# rev00.net
KiCad netlist of a schematic drawn in EAGLE
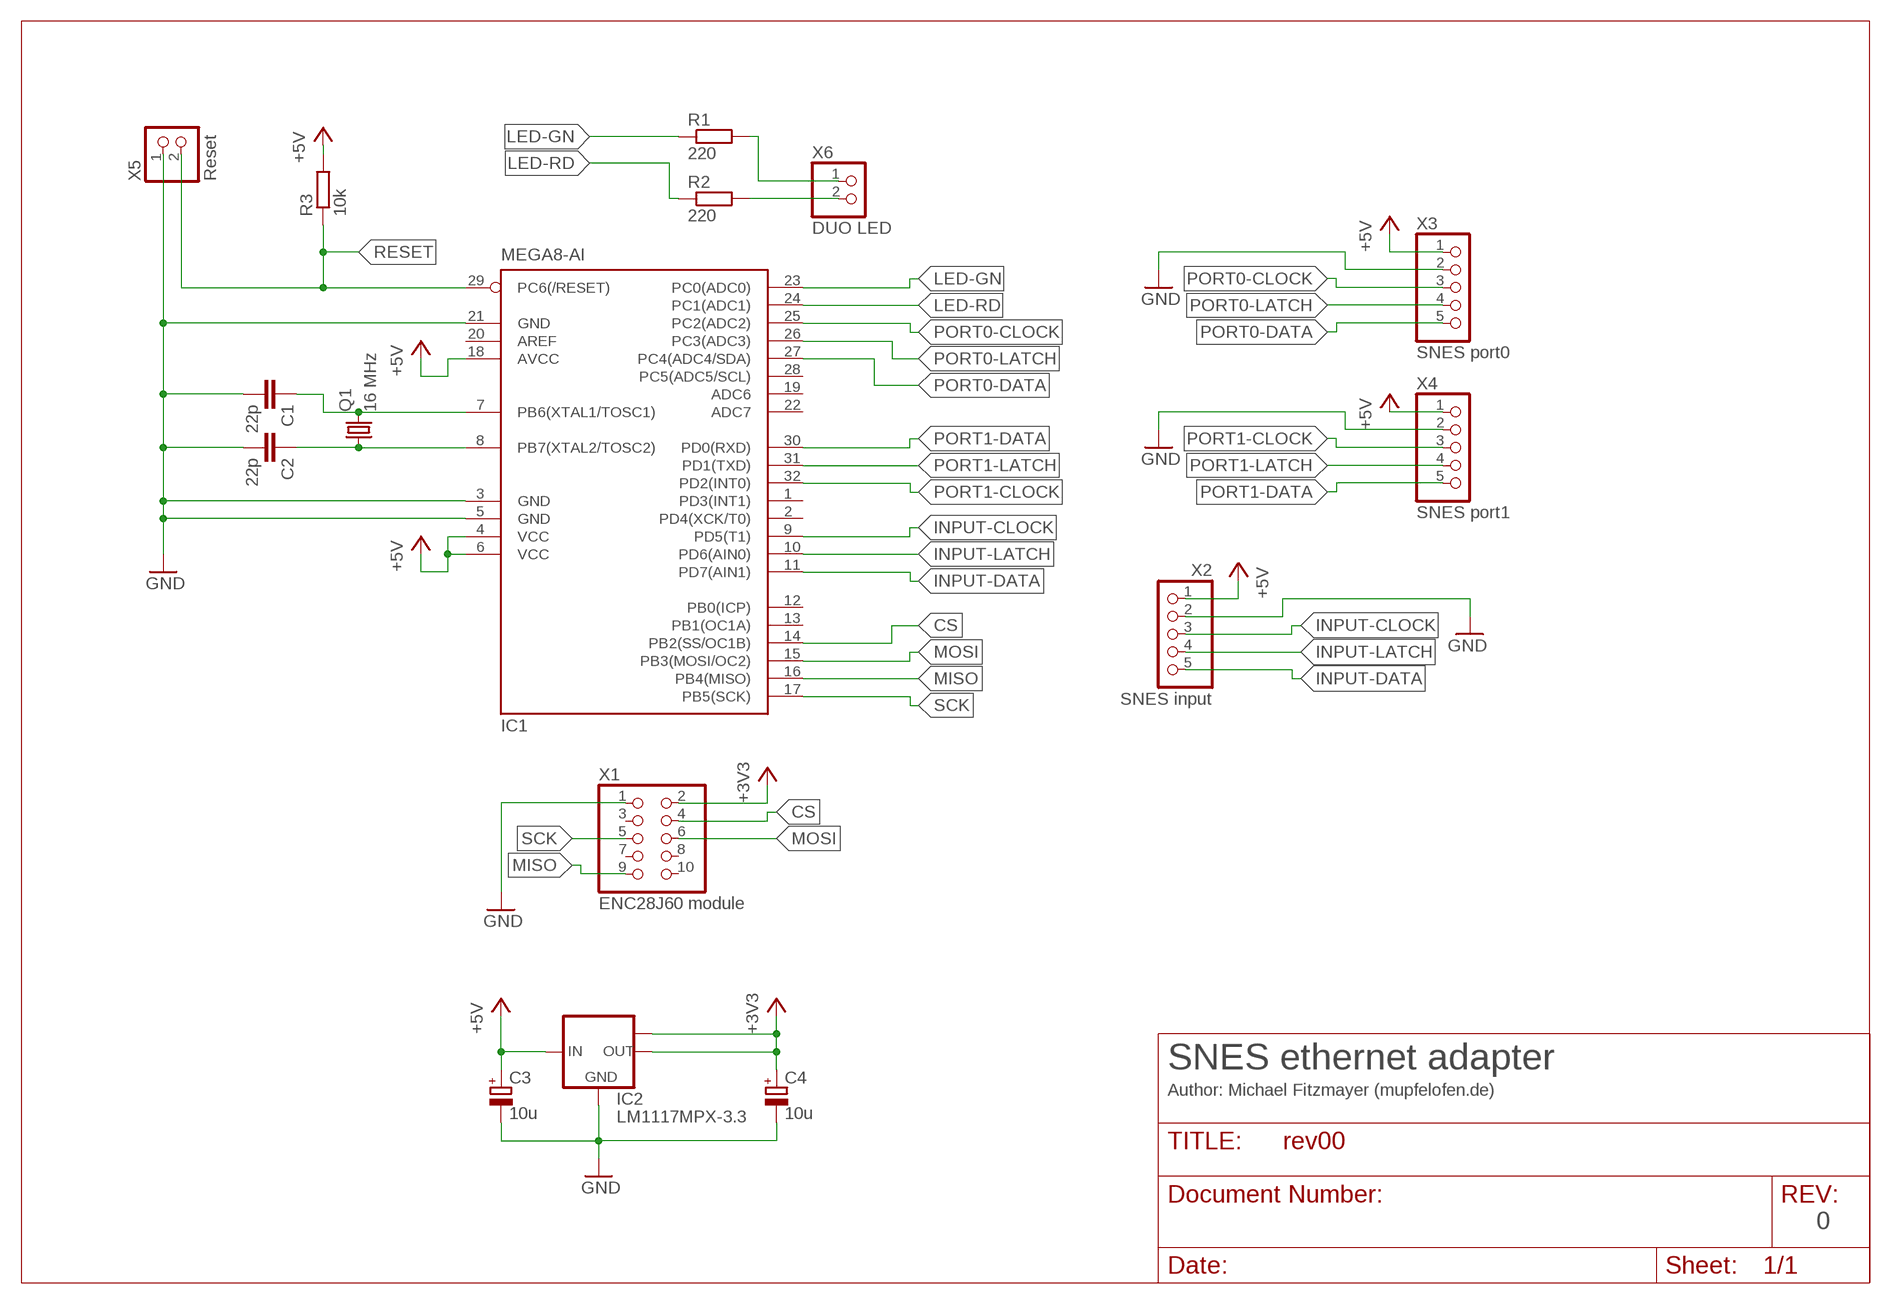
[diagram p0: schematic, sheet 1]

(export (version "E")
  (design (tool "Eeschema 10.0.6"))
  (components
    (comp (ref "C1")
      (value "22p")
      (footprint "eagle-import:C1206")
      (libsource (lib "eagle-import") (part "C-EUC1206"))
    )
    (comp (ref "C2")
      (value "22p")
      (footprint "eagle-import:C1206")
      (libsource (lib "eagle-import") (part "C-EUC1206"))
    )
    (comp (ref "C3")
      (value "10u")
      (footprint "eagle-import:C_6032-28R")
      (libsource (lib "eagle-import") (part "CPOL-EUC/6032-28R"))
    )
    (comp (ref "C4")
      (value "10u")
      (footprint "eagle-import:C_6032-28R")
      (libsource (lib "eagle-import") (part "CPOL-EUC/6032-28R"))
    )
    (comp (ref "IC1")
      (value "MEGA8-AI")
      (footprint "eagle-import:TQFP32-08")
      (fields (field (name "MPN") "ATMEGA8-16AU"))
      (libsource (lib "eagle-import") (part "MEGA8-AI"))
    )
    (comp (ref "IC2")
      (value "LM1117MPX-3.3")
      (footprint "eagle-import:SOT223")
      (libsource (lib "eagle-import") (part "LM1117MPX-3.3"))
    )
    (comp (ref "Q1")
      (value "16 MHz")
      (footprint "eagle-import:SM49")
      (libsource (lib "eagle-import") (part "CRYSTALSM49"))
    )
    (comp (ref "R1")
      (value "220")
      (footprint "eagle-import:R1206")
      (libsource (lib "eagle-import") (part "R-EU_R1206"))
    )
    (comp (ref "R2")
      (value "220")
      (footprint "eagle-import:R1206")
      (libsource (lib "eagle-import") (part "R-EU_R1206"))
    )
    (comp (ref "R3")
      (value "10k")
      (footprint "eagle-import:R1206")
      (libsource (lib "eagle-import") (part "R-EU_R1206"))
    )
    (comp (ref "X1")
      (value "ENC28J60 module")
      (footprint "eagle-import:2X05SMD")
      (libsource (lib "eagle-import") (part "PINHD-2X5_2.54-SMD"))
    )
    (comp (ref "X2")
      (value "SNES input")
      (footprint "eagle-import:1X05SMD")
      (libsource (lib "eagle-import") (part "PINHD-1X5_2.54-SMD"))
    )
    (comp (ref "X3")
      (value "SNES port0")
      (footprint "eagle-import:1X05SMD")
      (libsource (lib "eagle-import") (part "PINHD-1X5_2.54-SMD"))
    )
    (comp (ref "X4")
      (value "SNES port1")
      (footprint "eagle-import:1X05SMD")
      (libsource (lib "eagle-import") (part "PINHD-1X5_2.54-SMD"))
    )
    (comp (ref "X5")
      (value "Reset")
      (footprint "eagle-import:1X02SMD")
      (libsource (lib "eagle-import") (part "PINHD-1X2_2.54-SMD"))
    )
    (comp (ref "X6")
      (value "DUO LED")
      (footprint "eagle-import:1X02SMD")
      (libsource (lib "eagle-import") (part "PINHD-1X2_2.54-SMD"))
    )
  )
  (nets
    (net (code "1") (name "+3V3") (class "Default")
      (node (ref "C4") (pin "+") (pinfunction "+_+") (pintype "passive"))
      (node (ref "IC2") (pin "2") (pinfunction "OUT_2") (pintype "passive"))
      (node (ref "IC2") (pin "TAB") (pinfunction "OUT1_TAB") (pintype "passive"))
      (node (ref "X1") (pin "2") (pinfunction "2_2") (pintype "passive"))
    )
    (net (code "2") (name "+5V") (class "Default")
      (node (ref "C3") (pin "+") (pinfunction "+_+") (pintype "passive"))
      (node (ref "IC1") (pin "18") (pinfunction "AVCC_18") (pintype "power_in"))
      (node (ref "IC1") (pin "4") (pinfunction "VCC_4") (pintype "power_in"))
      (node (ref "IC1") (pin "6") (pinfunction "VCC_6") (pintype "power_in"))
      (node (ref "IC2") (pin "3") (pinfunction "IN_3") (pintype "input"))
      (node (ref "R3") (pin "2") (pinfunction "2_2") (pintype "passive"))
      (node (ref "X2") (pin "1") (pinfunction "1_1") (pintype "passive"))
      (node (ref "X3") (pin "1") (pinfunction "1_1") (pintype "passive"))
      (node (ref "X4") (pin "1") (pinfunction "1_1") (pintype "passive"))
    )
    (net (code "3") (name "CS") (class "Default")
      (node (ref "IC1") (pin "14") (pinfunction "PB2(SS/OC1B)_14") (pintype "bidirectional"))
      (node (ref "X1") (pin "4") (pinfunction "4_4") (pintype "passive"))
    )
    (net (code "4") (name "GND") (class "Default")
      (node (ref "C1") (pin "2") (pinfunction "2_2") (pintype "passive"))
      (node (ref "C2") (pin "2") (pinfunction "2_2") (pintype "passive"))
      (node (ref "C3") (pin "-") (pinfunction "-_-") (pintype "passive"))
      (node (ref "C4") (pin "-") (pinfunction "-_-") (pintype "passive"))
      (node (ref "IC1") (pin "21") (pinfunction "GND_21") (pintype "power_in"))
      (node (ref "IC1") (pin "3") (pinfunction "GND_3") (pintype "power_in"))
      (node (ref "IC1") (pin "5") (pinfunction "GND_5") (pintype "power_in"))
      (node (ref "IC2") (pin "1") (pinfunction "GND_1") (pintype "input"))
      (node (ref "X1") (pin "1") (pinfunction "1_1") (pintype "passive"))
      (node (ref "X2") (pin "2") (pinfunction "2_2") (pintype "passive"))
      (node (ref "X3") (pin "2") (pinfunction "2_2") (pintype "passive"))
      (node (ref "X4") (pin "2") (pinfunction "2_2") (pintype "passive"))
      (node (ref "X5") (pin "1") (pinfunction "1_1") (pintype "passive"))
    )
    (net (code "5") (name "INPUT-CLOCK") (class "Default")
      (node (ref "IC1") (pin "9") (pinfunction "PD5(T1)_9") (pintype "bidirectional"))
      (node (ref "X2") (pin "3") (pinfunction "3_3") (pintype "passive"))
    )
    (net (code "6") (name "INPUT-DATA") (class "Default")
      (node (ref "IC1") (pin "11") (pinfunction "PD7(AIN1)_11") (pintype "bidirectional"))
      (node (ref "X2") (pin "5") (pinfunction "5_5") (pintype "passive"))
    )
    (net (code "7") (name "INPUT-LATCH") (class "Default")
      (node (ref "IC1") (pin "10") (pinfunction "PD6(AIN0)_10") (pintype "bidirectional"))
      (node (ref "X2") (pin "4") (pinfunction "4_4") (pintype "passive"))
    )
    (net (code "8") (name "LED-GN") (class "Default")
      (node (ref "IC1") (pin "23") (pinfunction "PC0(ADC0)_23") (pintype "bidirectional"))
      (node (ref "R1") (pin "1") (pinfunction "1_1") (pintype "passive"))
    )
    (net (code "9") (name "LED-RD") (class "Default")
      (node (ref "IC1") (pin "24") (pinfunction "PC1(ADC1)_24") (pintype "bidirectional"))
      (node (ref "R2") (pin "1") (pinfunction "1_1") (pintype "passive"))
    )
    (net (code "10") (name "MISO") (class "Default")
      (node (ref "IC1") (pin "16") (pinfunction "PB4(MISO)_16") (pintype "bidirectional"))
      (node (ref "X1") (pin "9") (pinfunction "9_9") (pintype "passive"))
    )
    (net (code "11") (name "MOSI") (class "Default")
      (node (ref "IC1") (pin "15") (pinfunction "PB3(MOSI/OC2)_15") (pintype "bidirectional"))
      (node (ref "X1") (pin "6") (pinfunction "6_6") (pintype "passive"))
    )
    (net (code "12") (name "Net-(IC1-PB6(XTAL1{slash}TOSC1))") (class "Default")
      (node (ref "C1") (pin "1") (pinfunction "1_1") (pintype "passive"))
      (node (ref "IC1") (pin "7") (pinfunction "PB6(XTAL1/TOSC1)_7") (pintype "bidirectional"))
      (node (ref "Q1") (pin "2") (pinfunction "2_2") (pintype "passive"))
    )
    (net (code "13") (name "Net-(IC1-PB7(XTAL2{slash}TOSC2))") (class "Default")
      (node (ref "C2") (pin "1") (pinfunction "1_1") (pintype "passive"))
      (node (ref "IC1") (pin "8") (pinfunction "PB7(XTAL2/TOSC2)_8") (pintype "bidirectional"))
      (node (ref "Q1") (pin "1") (pinfunction "1_1") (pintype "passive"))
    )
    (net (code "14") (name "Net-(R1-Pad2)") (class "Default")
      (node (ref "R1") (pin "2") (pinfunction "2_2") (pintype "passive"))
      (node (ref "X6") (pin "1") (pinfunction "1_1") (pintype "passive"))
    )
    (net (code "15") (name "Net-(R2-Pad2)") (class "Default")
      (node (ref "R2") (pin "2") (pinfunction "2_2") (pintype "passive"))
      (node (ref "X6") (pin "2") (pinfunction "2_2") (pintype "passive"))
    )
    (net (code "16") (name "PORT0-CLOCK") (class "Default")
      (node (ref "IC1") (pin "25") (pinfunction "PC2(ADC2)_25") (pintype "bidirectional"))
      (node (ref "X3") (pin "3") (pinfunction "3_3") (pintype "passive"))
    )
    (net (code "17") (name "PORT0-DATA") (class "Default")
      (node (ref "IC1") (pin "27") (pinfunction "PC4(ADC4/SDA)_27") (pintype "bidirectional"))
      (node (ref "X3") (pin "5") (pinfunction "5_5") (pintype "passive"))
    )
    (net (code "18") (name "PORT0-LATCH") (class "Default")
      (node (ref "IC1") (pin "26") (pinfunction "PC3(ADC3)_26") (pintype "bidirectional"))
      (node (ref "X3") (pin "4") (pinfunction "4_4") (pintype "passive"))
    )
    (net (code "19") (name "PORT1-CLOCK") (class "Default")
      (node (ref "IC1") (pin "32") (pinfunction "PD2(INT0)_32") (pintype "bidirectional"))
      (node (ref "X4") (pin "3") (pinfunction "3_3") (pintype "passive"))
    )
    (net (code "20") (name "PORT1-DATA") (class "Default")
      (node (ref "IC1") (pin "30") (pinfunction "PD0(RXD)_30") (pintype "bidirectional"))
      (node (ref "X4") (pin "5") (pinfunction "5_5") (pintype "passive"))
    )
    (net (code "21") (name "PORT1-LATCH") (class "Default")
      (node (ref "IC1") (pin "31") (pinfunction "PD1(TXD)_31") (pintype "bidirectional"))
      (node (ref "X4") (pin "4") (pinfunction "4_4") (pintype "passive"))
    )
    (net (code "22") (name "RESET") (class "Default")
      (node (ref "IC1") (pin "29") (pinfunction "PC6(/RESET)_29") (pintype "bidirectional"))
      (node (ref "R3") (pin "1") (pinfunction "1_1") (pintype "passive"))
      (node (ref "X5") (pin "2") (pinfunction "2_2") (pintype "passive"))
    )
    (net (code "23") (name "SCK") (class "Default")
      (node (ref "IC1") (pin "17") (pinfunction "PB5(SCK)_17") (pintype "bidirectional"))
      (node (ref "X1") (pin "5") (pinfunction "5_5") (pintype "passive"))
    )
    (net (code "24") (name "unconnected-(IC1-ADC6-Pad19)") (class "Default")
      (node (ref "IC1") (pin "19") (pinfunction "ADC6_19") (pintype "bidirectional"))
    )
    (net (code "25") (name "unconnected-(IC1-ADC7-Pad22)") (class "Default")
      (node (ref "IC1") (pin "22") (pinfunction "ADC7_22") (pintype "bidirectional"))
    )
    (net (code "26") (name "unconnected-(IC1-AREF-Pad20)") (class "Default")
      (node (ref "IC1") (pin "20") (pinfunction "AREF_20") (pintype "passive"))
    )
    (net (code "27") (name "unconnected-(IC1-PB0(ICP)-Pad12)") (class "Default")
      (node (ref "IC1") (pin "12") (pinfunction "PB0(ICP)_12") (pintype "bidirectional"))
    )
    (net (code "28") (name "unconnected-(IC1-PB1(OC1A)-Pad13)") (class "Default")
      (node (ref "IC1") (pin "13") (pinfunction "PB1(OC1A)_13") (pintype "bidirectional"))
    )
    (net (code "29") (name "unconnected-(IC1-PC5(ADC5{slash}SCL)-Pad28)") (class "Default")
      (node (ref "IC1") (pin "28") (pinfunction "PC5(ADC5/SCL)_28") (pintype "bidirectional"))
    )
    (net (code "30") (name "unconnected-(IC1-PD3(INT1)-Pad1)") (class "Default")
      (node (ref "IC1") (pin "1") (pinfunction "PD3(INT1)_1") (pintype "bidirectional"))
    )
    (net (code "31") (name "unconnected-(IC1-PD4(XCK{slash}T0)-Pad2)") (class "Default")
      (node (ref "IC1") (pin "2") (pinfunction "PD4(XCK/T0)_2") (pintype "bidirectional"))
    )
    (net (code "32") (name "unconnected-(X1-Pad3)") (class "Default")
      (node (ref "X1") (pin "3") (pinfunction "3_3") (pintype "passive"))
    )
    (net (code "33") (name "unconnected-(X1-Pad7)") (class "Default")
      (node (ref "X1") (pin "7") (pinfunction "7_7") (pintype "passive"))
    )
    (net (code "34") (name "unconnected-(X1-Pad8)") (class "Default")
      (node (ref "X1") (pin "8") (pinfunction "8_8") (pintype "passive"))
    )
    (net (code "35") (name "unconnected-(X1-Pad10)") (class "Default")
      (node (ref "X1") (pin "10") (pinfunction "10_10") (pintype "passive"))
    )
  )
)
